# Connections_and_Power.net
KiCad netlist of a schematic drawn in EAGLE
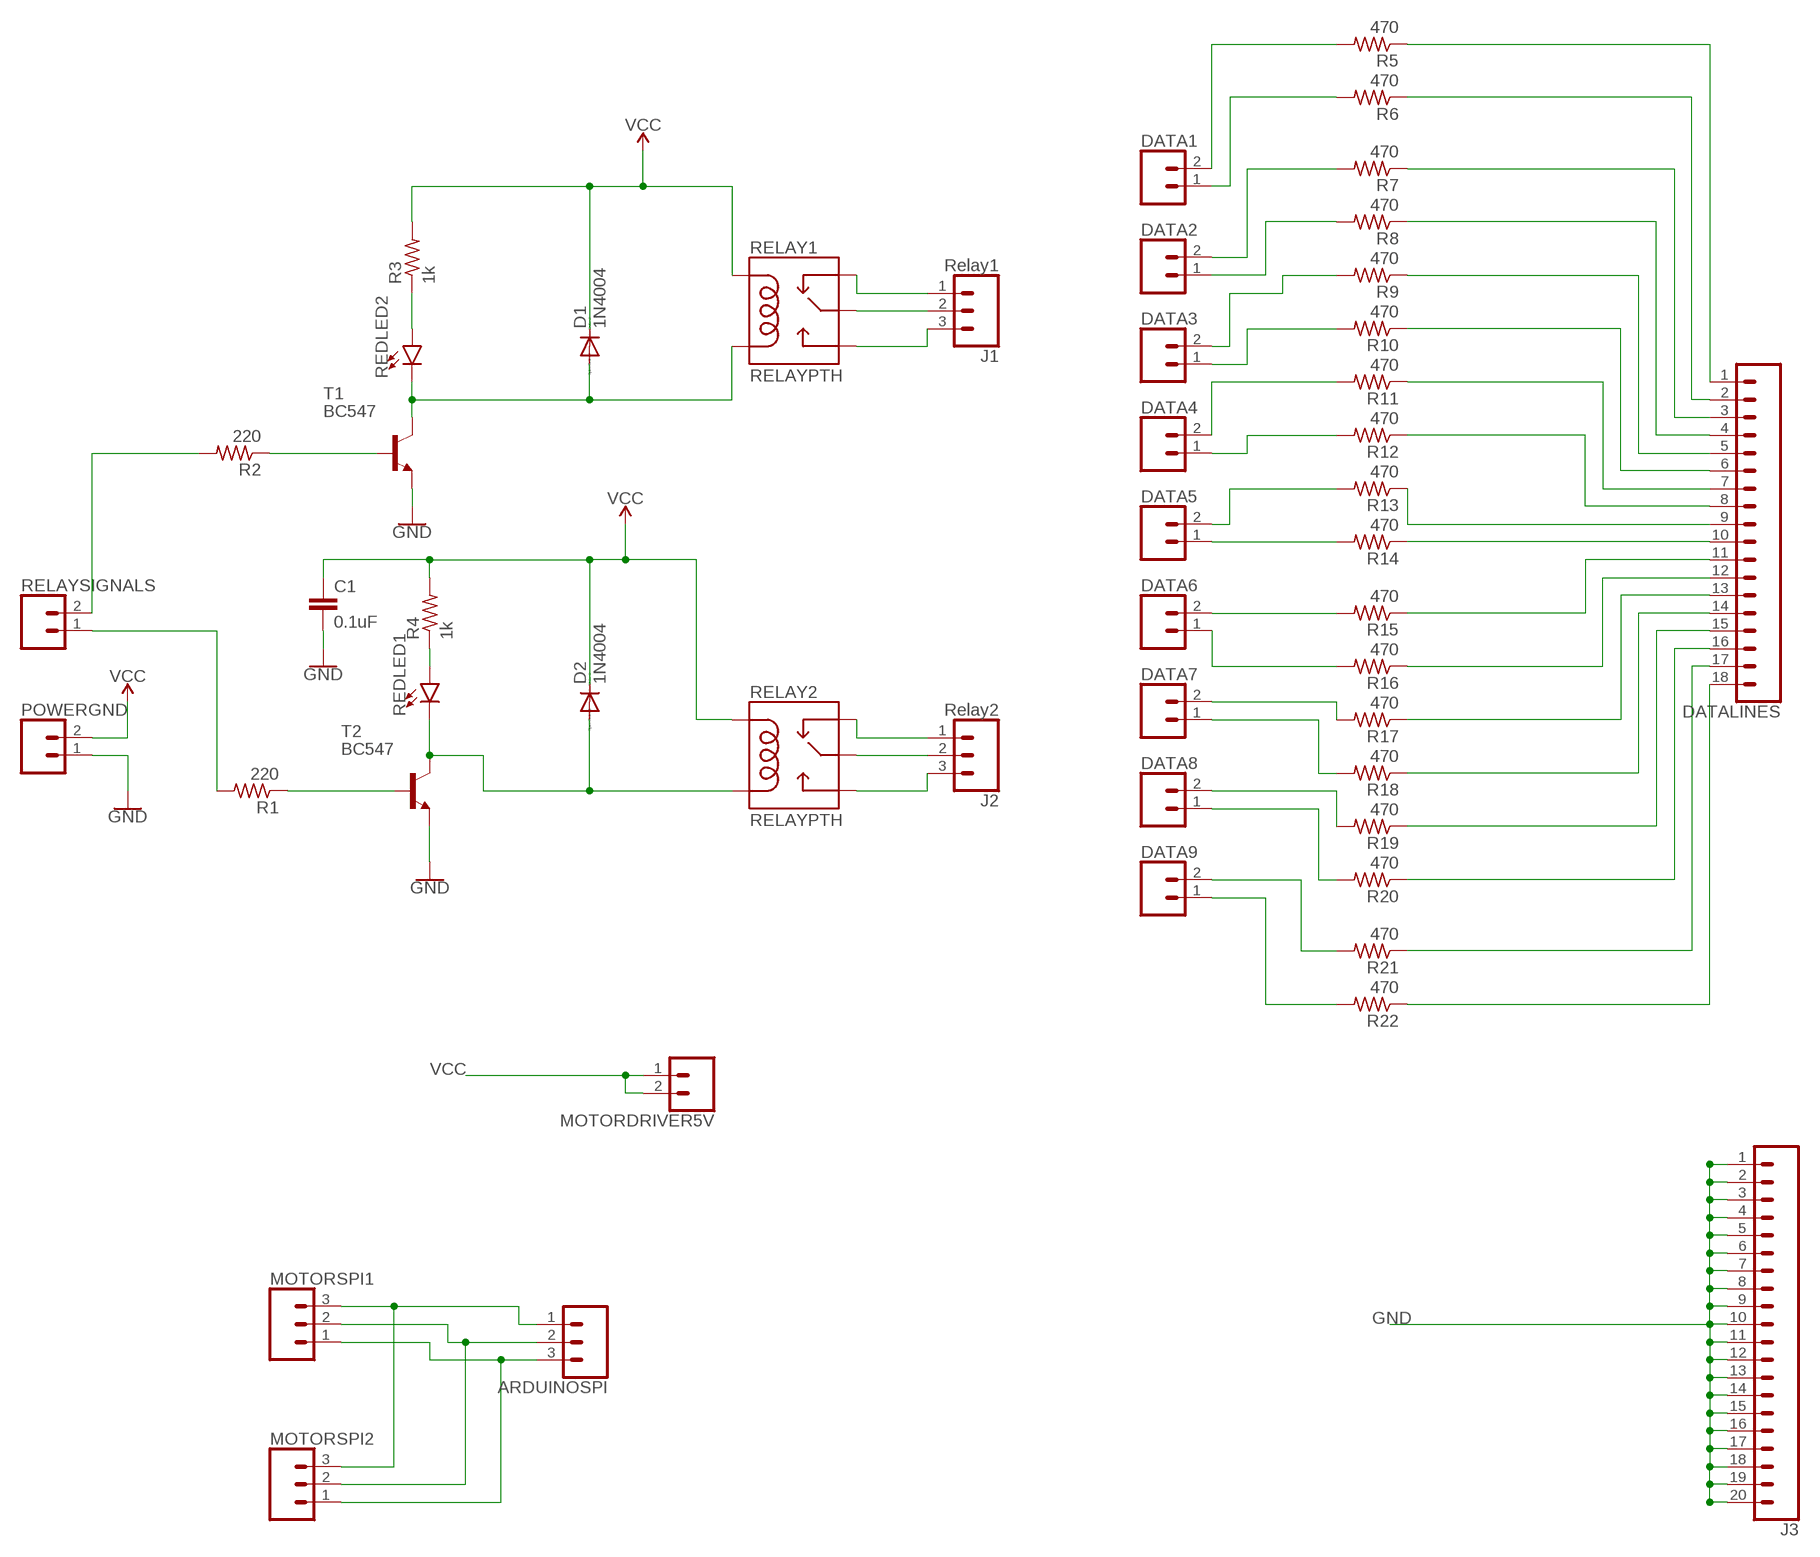
[diagram p0: schematic, sheet 1]

(export (version "E")
  (design (tool "Eeschema 10.0.6"))
  (components
    (comp (ref "ARDUINOSPI")
      (value "CONN_03")
      (footprint "eagle-import:1X03")
      (libsource (lib "eagle-import") (part "CONN_03"))
    )
    (comp (ref "C1")
      (value "0.1uF")
      (footprint "eagle-import:CAP-PTH-SMALL-KIT")
      (libsource (lib "eagle-import") (part "0.1UF-KIT-EZ-50V-20%"))
    )
    (comp (ref "D1")
      (value "1N4004")
      (footprint "eagle-import:DO41-10")
      (libsource (lib "eagle-import") (part "1N4004"))
    )
    (comp (ref "D2")
      (value "1N4004")
      (footprint "eagle-import:DO41-10")
      (libsource (lib "eagle-import") (part "1N4004"))
    )
    (comp (ref "DATA1")
      (value "CONN_023.5MM")
      (footprint "eagle-import:SCREWTERMINAL-3.5MM-2")
      (libsource (lib "eagle-import") (part "CONN_023.5MM"))
    )
    (comp (ref "DATA2")
      (value "CONN_023.5MM")
      (footprint "eagle-import:SCREWTERMINAL-3.5MM-2")
      (libsource (lib "eagle-import") (part "CONN_023.5MM"))
    )
    (comp (ref "DATA3")
      (value "CONN_023.5MM")
      (footprint "eagle-import:SCREWTERMINAL-3.5MM-2")
      (libsource (lib "eagle-import") (part "CONN_023.5MM"))
    )
    (comp (ref "DATA4")
      (value "CONN_023.5MM")
      (footprint "eagle-import:SCREWTERMINAL-3.5MM-2")
      (libsource (lib "eagle-import") (part "CONN_023.5MM"))
    )
    (comp (ref "DATA5")
      (value "CONN_023.5MM")
      (footprint "eagle-import:SCREWTERMINAL-3.5MM-2")
      (libsource (lib "eagle-import") (part "CONN_023.5MM"))
    )
    (comp (ref "DATA6")
      (value "CONN_023.5MM")
      (footprint "eagle-import:SCREWTERMINAL-3.5MM-2")
      (libsource (lib "eagle-import") (part "CONN_023.5MM"))
    )
    (comp (ref "DATA7")
      (value "CONN_023.5MM")
      (footprint "eagle-import:SCREWTERMINAL-3.5MM-2")
      (libsource (lib "eagle-import") (part "CONN_023.5MM"))
    )
    (comp (ref "DATA8")
      (value "CONN_023.5MM")
      (footprint "eagle-import:SCREWTERMINAL-3.5MM-2")
      (libsource (lib "eagle-import") (part "CONN_023.5MM"))
    )
    (comp (ref "DATA9")
      (value "CONN_023.5MM")
      (footprint "eagle-import:SCREWTERMINAL-3.5MM-2")
      (libsource (lib "eagle-import") (part "CONN_023.5MM"))
    )
    (comp (ref "DATALINES")
      (value "CONN_18")
      (footprint "eagle-import:1X18")
      (libsource (lib "eagle-import") (part "CONN_18"))
    )
    (comp (ref "J1")
      (value "Relay1")
      (footprint "eagle-import:SCREWTERMINAL-5MM-3")
      (libsource (lib "eagle-import") (part "CONN_03-SCREW-5MM"))
    )
    (comp (ref "J2")
      (value "Relay2")
      (footprint "eagle-import:SCREWTERMINAL-5MM-3")
      (libsource (lib "eagle-import") (part "CONN_03-SCREW-5MM"))
    )
    (comp (ref "J3")
      (value "CONN_20")
      (footprint "eagle-import:1X20")
      (libsource (lib "eagle-import") (part "CONN_20"))
    )
    (comp (ref "MOTORDRIVER5V")
      (value "CONN_02")
      (footprint "eagle-import:1X02")
      (libsource (lib "eagle-import") (part "CONN_02"))
    )
    (comp (ref "MOTORSPI1")
      (value "CONN_03")
      (footprint "eagle-import:1X03")
      (libsource (lib "eagle-import") (part "CONN_03"))
    )
    (comp (ref "MOTORSPI2")
      (value "CONN_03")
      (footprint "eagle-import:1X03")
      (libsource (lib "eagle-import") (part "CONN_03"))
    )
    (comp (ref "POWERGND")
      (value "CONN_025MM")
      (footprint "eagle-import:SCREWTERMINAL-5MM-2")
      (libsource (lib "eagle-import") (part "CONN_025MM"))
    )
    (comp (ref "R1")
      (value "220")
      (footprint "eagle-import:0309_12")
      (libsource (lib "eagle-import") (part "R-US_0309/12"))
    )
    (comp (ref "R2")
      (value "220")
      (footprint "eagle-import:0309_12")
      (libsource (lib "eagle-import") (part "R-US_0309/12"))
    )
    (comp (ref "R3")
      (value "1k")
      (footprint "eagle-import:0309_12")
      (libsource (lib "eagle-import") (part "R-US_0309/12"))
    )
    (comp (ref "R4")
      (value "1k")
      (footprint "eagle-import:0309_12")
      (libsource (lib "eagle-import") (part "R-US_0309/12"))
    )
    (comp (ref "R5")
      (value "470")
      (footprint "eagle-import:0309_12")
      (libsource (lib "eagle-import") (part "R-US_0309/12"))
    )
    (comp (ref "R6")
      (value "470")
      (footprint "eagle-import:0309_12")
      (libsource (lib "eagle-import") (part "R-US_0309/12"))
    )
    (comp (ref "R7")
      (value "470")
      (footprint "eagle-import:0309_12")
      (libsource (lib "eagle-import") (part "R-US_0309/12"))
    )
    (comp (ref "R8")
      (value "470")
      (footprint "eagle-import:0309_12")
      (libsource (lib "eagle-import") (part "R-US_0309/12"))
    )
    (comp (ref "R9")
      (value "470")
      (footprint "eagle-import:0309_12")
      (libsource (lib "eagle-import") (part "R-US_0309/12"))
    )
    (comp (ref "R10")
      (value "470")
      (footprint "eagle-import:0309_12")
      (libsource (lib "eagle-import") (part "R-US_0309/12"))
    )
    (comp (ref "R11")
      (value "470")
      (footprint "eagle-import:0309_12")
      (libsource (lib "eagle-import") (part "R-US_0309/12"))
    )
    (comp (ref "R12")
      (value "470")
      (footprint "eagle-import:0309_12")
      (libsource (lib "eagle-import") (part "R-US_0309/12"))
    )
    (comp (ref "R13")
      (value "470")
      (footprint "eagle-import:0309_12")
      (libsource (lib "eagle-import") (part "R-US_0309/12"))
    )
    (comp (ref "R14")
      (value "470")
      (footprint "eagle-import:0309_12")
      (libsource (lib "eagle-import") (part "R-US_0309/12"))
    )
    (comp (ref "R15")
      (value "470")
      (footprint "eagle-import:0309_12")
      (libsource (lib "eagle-import") (part "R-US_0309/12"))
    )
    (comp (ref "R16")
      (value "470")
      (footprint "eagle-import:0309_12")
      (libsource (lib "eagle-import") (part "R-US_0309/12"))
    )
    (comp (ref "R17")
      (value "470")
      (footprint "eagle-import:0309_12")
      (libsource (lib "eagle-import") (part "R-US_0309/12"))
    )
    (comp (ref "R18")
      (value "470")
      (footprint "eagle-import:0309_12")
      (libsource (lib "eagle-import") (part "R-US_0309/12"))
    )
    (comp (ref "R19")
      (value "470")
      (footprint "eagle-import:0309_12")
      (libsource (lib "eagle-import") (part "R-US_0309/12"))
    )
    (comp (ref "R20")
      (value "470")
      (footprint "eagle-import:0309_12")
      (libsource (lib "eagle-import") (part "R-US_0309/12"))
    )
    (comp (ref "R21")
      (value "470")
      (footprint "eagle-import:0309_12")
      (libsource (lib "eagle-import") (part "R-US_0309/12"))
    )
    (comp (ref "R22")
      (value "470")
      (footprint "eagle-import:0309_12")
      (libsource (lib "eagle-import") (part "R-US_0309/12"))
    )
    (comp (ref "REDLED1")
      (value "LED1206")
      (footprint "eagle-import:LED-1206")
      (libsource (lib "eagle-import") (part "LED1206"))
    )
    (comp (ref "REDLED2")
      (value "LED1206")
      (footprint "eagle-import:LED-1206")
      (libsource (lib "eagle-import") (part "LED1206"))
    )
    (comp (ref "RELAY1")
      (value "RELAYPTH")
      (footprint "eagle-import:SRD-05VDC-SL-C")
      (libsource (lib "eagle-import") (part "RELAYPTH"))
    )
    (comp (ref "RELAY2")
      (value "RELAYPTH")
      (footprint "eagle-import:SRD-05VDC-SL-C")
      (libsource (lib "eagle-import") (part "RELAYPTH"))
    )
    (comp (ref "RELAYSIGNALS")
      (value "CONN_025MM")
      (footprint "eagle-import:SCREWTERMINAL-5MM-2")
      (libsource (lib "eagle-import") (part "CONN_025MM"))
    )
    (comp (ref "T1")
      (value "BC547")
      (footprint "eagle-import:TO92")
      (libsource (lib "eagle-import") (part "BC547"))
    )
    (comp (ref "T2")
      (value "BC547")
      (footprint "eagle-import:TO92")
      (libsource (lib "eagle-import") (part "BC547"))
    )
  )
  (nets
    (net (code "1") (name "GND") (class "Default")
      (node (ref "C1") (pin "2") (pinfunction "2_2") (pintype "passive"))
      (node (ref "J3") (pin "1") (pinfunction "1_1") (pintype "passive"))
      (node (ref "J3") (pin "10") (pinfunction "10_10") (pintype "passive"))
      (node (ref "J3") (pin "11") (pinfunction "11_11") (pintype "passive"))
      (node (ref "J3") (pin "12") (pinfunction "12_12") (pintype "passive"))
      (node (ref "J3") (pin "13") (pinfunction "13_13") (pintype "passive"))
      (node (ref "J3") (pin "14") (pinfunction "14_14") (pintype "passive"))
      (node (ref "J3") (pin "15") (pinfunction "15_15") (pintype "passive"))
      (node (ref "J3") (pin "16") (pinfunction "16_16") (pintype "passive"))
      (node (ref "J3") (pin "17") (pinfunction "17_17") (pintype "passive"))
      (node (ref "J3") (pin "18") (pinfunction "18_18") (pintype "passive"))
      (node (ref "J3") (pin "19") (pinfunction "19_19") (pintype "passive"))
      (node (ref "J3") (pin "2") (pinfunction "2_2") (pintype "passive"))
      (node (ref "J3") (pin "20") (pinfunction "20_20") (pintype "passive"))
      (node (ref "J3") (pin "3") (pinfunction "3_3") (pintype "passive"))
      (node (ref "J3") (pin "4") (pinfunction "4_4") (pintype "passive"))
      (node (ref "J3") (pin "5") (pinfunction "5_5") (pintype "passive"))
      (node (ref "J3") (pin "6") (pinfunction "6_6") (pintype "passive"))
      (node (ref "J3") (pin "7") (pinfunction "7_7") (pintype "passive"))
      (node (ref "J3") (pin "8") (pinfunction "8_8") (pintype "passive"))
      (node (ref "J3") (pin "9") (pinfunction "9_9") (pintype "passive"))
      (node (ref "POWERGND") (pin "1") (pinfunction "1_1") (pintype "passive"))
      (node (ref "T1") (pin "1") (pinfunction "E_1") (pintype "passive"))
      (node (ref "T2") (pin "1") (pinfunction "E_1") (pintype "passive"))
    )
    (net (code "2") (name "Net-(ARDUINOSPI-Pad1)") (class "Default")
      (node (ref "ARDUINOSPI") (pin "1") (pinfunction "1_1") (pintype "passive"))
      (node (ref "MOTORSPI1") (pin "3") (pinfunction "3_3") (pintype "passive"))
      (node (ref "MOTORSPI2") (pin "3") (pinfunction "3_3") (pintype "passive"))
    )
    (net (code "3") (name "Net-(ARDUINOSPI-Pad2)") (class "Default")
      (node (ref "ARDUINOSPI") (pin "2") (pinfunction "2_2") (pintype "passive"))
      (node (ref "MOTORSPI1") (pin "2") (pinfunction "2_2") (pintype "passive"))
      (node (ref "MOTORSPI2") (pin "2") (pinfunction "2_2") (pintype "passive"))
    )
    (net (code "4") (name "Net-(ARDUINOSPI-Pad3)") (class "Default")
      (node (ref "ARDUINOSPI") (pin "3") (pinfunction "3_3") (pintype "passive"))
      (node (ref "MOTORSPI1") (pin "1") (pinfunction "1_1") (pintype "passive"))
      (node (ref "MOTORSPI2") (pin "1") (pinfunction "1_1") (pintype "passive"))
    )
    (net (code "5") (name "Net-(DATA1-Pad1)") (class "Default")
      (node (ref "DATA1") (pin "1") (pinfunction "1_1") (pintype "passive"))
      (node (ref "R6") (pin "2") (pinfunction "2_2") (pintype "passive"))
    )
    (net (code "6") (name "Net-(DATA1-Pad2)") (class "Default")
      (node (ref "DATA1") (pin "2") (pinfunction "2_2") (pintype "passive"))
      (node (ref "R5") (pin "2") (pinfunction "2_2") (pintype "passive"))
    )
    (net (code "7") (name "Net-(DATA2-Pad1)") (class "Default")
      (node (ref "DATA2") (pin "1") (pinfunction "1_1") (pintype "passive"))
      (node (ref "R8") (pin "2") (pinfunction "2_2") (pintype "passive"))
    )
    (net (code "8") (name "Net-(DATA2-Pad2)") (class "Default")
      (node (ref "DATA2") (pin "2") (pinfunction "2_2") (pintype "passive"))
      (node (ref "R7") (pin "2") (pinfunction "2_2") (pintype "passive"))
    )
    (net (code "9") (name "Net-(DATA3-Pad1)") (class "Default")
      (node (ref "DATA3") (pin "1") (pinfunction "1_1") (pintype "passive"))
      (node (ref "R10") (pin "2") (pinfunction "2_2") (pintype "passive"))
    )
    (net (code "10") (name "Net-(DATA3-Pad2)") (class "Default")
      (node (ref "DATA3") (pin "2") (pinfunction "2_2") (pintype "passive"))
      (node (ref "R9") (pin "2") (pinfunction "2_2") (pintype "passive"))
    )
    (net (code "11") (name "Net-(DATA4-Pad1)") (class "Default")
      (node (ref "DATA4") (pin "1") (pinfunction "1_1") (pintype "passive"))
      (node (ref "R12") (pin "2") (pinfunction "2_2") (pintype "passive"))
    )
    (net (code "12") (name "Net-(DATA4-Pad2)") (class "Default")
      (node (ref "DATA4") (pin "2") (pinfunction "2_2") (pintype "passive"))
      (node (ref "R11") (pin "2") (pinfunction "2_2") (pintype "passive"))
    )
    (net (code "13") (name "Net-(DATA5-Pad1)") (class "Default")
      (node (ref "DATA5") (pin "1") (pinfunction "1_1") (pintype "passive"))
      (node (ref "R14") (pin "2") (pinfunction "2_2") (pintype "passive"))
    )
    (net (code "14") (name "Net-(DATA5-Pad2)") (class "Default")
      (node (ref "DATA5") (pin "2") (pinfunction "2_2") (pintype "passive"))
      (node (ref "R13") (pin "2") (pinfunction "2_2") (pintype "passive"))
    )
    (net (code "15") (name "Net-(DATA6-Pad1)") (class "Default")
      (node (ref "DATA6") (pin "1") (pinfunction "1_1") (pintype "passive"))
      (node (ref "R16") (pin "2") (pinfunction "2_2") (pintype "passive"))
    )
    (net (code "16") (name "Net-(DATA6-Pad2)") (class "Default")
      (node (ref "DATA6") (pin "2") (pinfunction "2_2") (pintype "passive"))
      (node (ref "R15") (pin "2") (pinfunction "2_2") (pintype "passive"))
    )
    (net (code "17") (name "Net-(DATA7-Pad1)") (class "Default")
      (node (ref "DATA7") (pin "1") (pinfunction "1_1") (pintype "passive"))
      (node (ref "R18") (pin "2") (pinfunction "2_2") (pintype "passive"))
    )
    (net (code "18") (name "Net-(DATA7-Pad2)") (class "Default")
      (node (ref "DATA7") (pin "2") (pinfunction "2_2") (pintype "passive"))
      (node (ref "R17") (pin "2") (pinfunction "2_2") (pintype "passive"))
    )
    (net (code "19") (name "Net-(DATA8-Pad1)") (class "Default")
      (node (ref "DATA8") (pin "1") (pinfunction "1_1") (pintype "passive"))
      (node (ref "R20") (pin "2") (pinfunction "2_2") (pintype "passive"))
    )
    (net (code "20") (name "Net-(DATA8-Pad2)") (class "Default")
      (node (ref "DATA8") (pin "2") (pinfunction "2_2") (pintype "passive"))
      (node (ref "R19") (pin "2") (pinfunction "2_2") (pintype "passive"))
    )
    (net (code "21") (name "Net-(DATA9-Pad1)") (class "Default")
      (node (ref "DATA9") (pin "1") (pinfunction "1_1") (pintype "passive"))
      (node (ref "R22") (pin "2") (pinfunction "2_2") (pintype "passive"))
    )
    (net (code "22") (name "Net-(DATA9-Pad2)") (class "Default")
      (node (ref "DATA9") (pin "2") (pinfunction "2_2") (pintype "passive"))
      (node (ref "R21") (pin "2") (pinfunction "2_2") (pintype "passive"))
    )
    (net (code "23") (name "Net-(DATALINES-Pad1)") (class "Default")
      (node (ref "DATALINES") (pin "1") (pinfunction "1_1") (pintype "passive"))
      (node (ref "R5") (pin "1") (pinfunction "1_1") (pintype "passive"))
    )
    (net (code "24") (name "Net-(DATALINES-Pad2)") (class "Default")
      (node (ref "DATALINES") (pin "2") (pinfunction "2_2") (pintype "passive"))
      (node (ref "R6") (pin "1") (pinfunction "1_1") (pintype "passive"))
    )
    (net (code "25") (name "Net-(DATALINES-Pad3)") (class "Default")
      (node (ref "DATALINES") (pin "3") (pinfunction "3_3") (pintype "passive"))
      (node (ref "R7") (pin "1") (pinfunction "1_1") (pintype "passive"))
    )
    (net (code "26") (name "Net-(DATALINES-Pad4)") (class "Default")
      (node (ref "DATALINES") (pin "4") (pinfunction "4_4") (pintype "passive"))
      (node (ref "R8") (pin "1") (pinfunction "1_1") (pintype "passive"))
    )
    (net (code "27") (name "Net-(DATALINES-Pad5)") (class "Default")
      (node (ref "DATALINES") (pin "5") (pinfunction "5_5") (pintype "passive"))
      (node (ref "R9") (pin "1") (pinfunction "1_1") (pintype "passive"))
    )
    (net (code "28") (name "Net-(DATALINES-Pad6)") (class "Default")
      (node (ref "DATALINES") (pin "6") (pinfunction "6_6") (pintype "passive"))
      (node (ref "R10") (pin "1") (pinfunction "1_1") (pintype "passive"))
    )
    (net (code "29") (name "Net-(DATALINES-Pad7)") (class "Default")
      (node (ref "DATALINES") (pin "7") (pinfunction "7_7") (pintype "passive"))
      (node (ref "R11") (pin "1") (pinfunction "1_1") (pintype "passive"))
    )
    (net (code "30") (name "Net-(DATALINES-Pad8)") (class "Default")
      (node (ref "DATALINES") (pin "8") (pinfunction "8_8") (pintype "passive"))
      (node (ref "R12") (pin "1") (pinfunction "1_1") (pintype "passive"))
    )
    (net (code "31") (name "Net-(DATALINES-Pad9)") (class "Default")
      (node (ref "DATALINES") (pin "9") (pinfunction "9_9") (pintype "passive"))
      (node (ref "R13") (pin "1") (pinfunction "1_1") (pintype "passive"))
    )
    (net (code "32") (name "Net-(DATALINES-Pad10)") (class "Default")
      (node (ref "DATALINES") (pin "10") (pinfunction "10_10") (pintype "passive"))
      (node (ref "R14") (pin "1") (pinfunction "1_1") (pintype "passive"))
    )
    (net (code "33") (name "Net-(DATALINES-Pad11)") (class "Default")
      (node (ref "DATALINES") (pin "11") (pinfunction "11_11") (pintype "passive"))
      (node (ref "R15") (pin "1") (pinfunction "1_1") (pintype "passive"))
    )
    (net (code "34") (name "Net-(DATALINES-Pad12)") (class "Default")
      (node (ref "DATALINES") (pin "12") (pinfunction "12_12") (pintype "passive"))
      (node (ref "R16") (pin "1") (pinfunction "1_1") (pintype "passive"))
    )
    (net (code "35") (name "Net-(DATALINES-Pad13)") (class "Default")
      (node (ref "DATALINES") (pin "13") (pinfunction "13_13") (pintype "passive"))
      (node (ref "R17") (pin "1") (pinfunction "1_1") (pintype "passive"))
    )
    (net (code "36") (name "Net-(DATALINES-Pad14)") (class "Default")
      (node (ref "DATALINES") (pin "14") (pinfunction "14_14") (pintype "passive"))
      (node (ref "R18") (pin "1") (pinfunction "1_1") (pintype "passive"))
    )
    (net (code "37") (name "Net-(DATALINES-Pad15)") (class "Default")
      (node (ref "DATALINES") (pin "15") (pinfunction "15_15") (pintype "passive"))
      (node (ref "R19") (pin "1") (pinfunction "1_1") (pintype "passive"))
    )
    (net (code "38") (name "Net-(DATALINES-Pad16)") (class "Default")
      (node (ref "DATALINES") (pin "16") (pinfunction "16_16") (pintype "passive"))
      (node (ref "R20") (pin "1") (pinfunction "1_1") (pintype "passive"))
    )
    (net (code "39") (name "Net-(DATALINES-Pad17)") (class "Default")
      (node (ref "DATALINES") (pin "17") (pinfunction "17_17") (pintype "passive"))
      (node (ref "R21") (pin "1") (pinfunction "1_1") (pintype "passive"))
    )
    (net (code "40") (name "Net-(DATALINES-Pad18)") (class "Default")
      (node (ref "DATALINES") (pin "18") (pinfunction "18_18") (pintype "passive"))
      (node (ref "R22") (pin "1") (pinfunction "1_1") (pintype "passive"))
    )
    (net (code "41") (name "Net-(J1-Pad2)") (class "Default")
      (node (ref "J1") (pin "2") (pinfunction "2_2") (pintype "passive"))
      (node (ref "RELAY1") (pin "SWCOMMON") (pinfunction "SWCOMMON_SWCOMMON") (pintype "bidirectional"))
    )
    (net (code "42") (name "Net-(J1-Pad3)") (class "Default")
      (node (ref "J1") (pin "3") (pinfunction "3_3") (pintype "passive"))
      (node (ref "RELAY1") (pin "SWOPEN") (pinfunction "SWOPEN_SWOPEN") (pintype "bidirectional"))
    )
    (net (code "43") (name "Net-(J2-Pad2)") (class "Default")
      (node (ref "J2") (pin "2") (pinfunction "2_2") (pintype "passive"))
      (node (ref "RELAY2") (pin "SWCOMMON") (pinfunction "SWCOMMON_SWCOMMON") (pintype "bidirectional"))
    )
    (net (code "44") (name "Net-(J2-Pad3)") (class "Default")
      (node (ref "J2") (pin "3") (pinfunction "3_3") (pintype "passive"))
      (node (ref "RELAY2") (pin "SWOPEN") (pinfunction "SWOPEN_SWOPEN") (pintype "bidirectional"))
    )
    (net (code "45") (name "Net-(R1-Pad2)") (class "Default")
      (node (ref "R1") (pin "2") (pinfunction "2_2") (pintype "passive"))
      (node (ref "RELAYSIGNALS") (pin "1") (pinfunction "1_1") (pintype "passive"))
    )
    (net (code "46") (name "Net-(R2-Pad2)") (class "Default")
      (node (ref "R2") (pin "2") (pinfunction "2_2") (pintype "passive"))
      (node (ref "RELAYSIGNALS") (pin "2") (pinfunction "2_2") (pintype "passive"))
    )
    (net (code "47") (name "Net-(R3-Pad1)") (class "Default")
      (node (ref "R3") (pin "1") (pinfunction "1_1") (pintype "passive"))
      (node (ref "REDLED2") (pin "A") (pinfunction "A_A") (pintype "passive"))
    )
    (net (code "48") (name "Net-(R4-Pad1)") (class "Default")
      (node (ref "R4") (pin "1") (pinfunction "1_1") (pintype "passive"))
      (node (ref "REDLED1") (pin "A") (pinfunction "A_A") (pintype "passive"))
    )
    (net (code "49") (name "Net-(RELAY1-SWCLOSE)") (class "Default")
      (node (ref "J1") (pin "1") (pinfunction "1_1") (pintype "passive"))
      (node (ref "RELAY1") (pin "SWCLOSED") (pinfunction "SWCLOSE_SWCLOSED") (pintype "bidirectional"))
    )
    (net (code "50") (name "Net-(RELAY2-SWCLOSE)") (class "Default")
      (node (ref "J2") (pin "1") (pinfunction "1_1") (pintype "passive"))
      (node (ref "RELAY2") (pin "SWCLOSED") (pinfunction "SWCLOSE_SWCLOSED") (pintype "bidirectional"))
    )
    (net (code "51") (name "Net-(T1-B)") (class "Default")
      (node (ref "R2") (pin "1") (pinfunction "1_1") (pintype "passive"))
      (node (ref "T1") (pin "2") (pinfunction "B_2") (pintype "passive"))
    )
    (net (code "52") (name "Net-(T1-C)") (class "Default")
      (node (ref "D1") (pin "A") (pinfunction "A_A") (pintype "passive"))
      (node (ref "REDLED2") (pin "C") (pinfunction "C_C") (pintype "passive"))
      (node (ref "RELAY1") (pin "COIL0") (pinfunction "COIL0_COIL0") (pintype "bidirectional"))
      (node (ref "T1") (pin "3") (pinfunction "C_3") (pintype "passive"))
    )
    (net (code "53") (name "Net-(T2-B)") (class "Default")
      (node (ref "R1") (pin "1") (pinfunction "1_1") (pintype "passive"))
      (node (ref "T2") (pin "2") (pinfunction "B_2") (pintype "passive"))
    )
    (net (code "54") (name "Net-(T2-C)") (class "Default")
      (node (ref "D2") (pin "A") (pinfunction "A_A") (pintype "passive"))
      (node (ref "REDLED1") (pin "C") (pinfunction "C_C") (pintype "passive"))
      (node (ref "RELAY2") (pin "COIL0") (pinfunction "COIL0_COIL0") (pintype "bidirectional"))
      (node (ref "T2") (pin "3") (pinfunction "C_3") (pintype "passive"))
    )
    (net (code "55") (name "VCC") (class "Default")
      (node (ref "C1") (pin "1") (pinfunction "1_1") (pintype "passive"))
      (node (ref "D1") (pin "C") (pinfunction "C_C") (pintype "passive"))
      (node (ref "D2") (pin "C") (pinfunction "C_C") (pintype "passive"))
      (node (ref "MOTORDRIVER5V") (pin "1") (pinfunction "1_1") (pintype "passive"))
      (node (ref "MOTORDRIVER5V") (pin "2") (pinfunction "2_2") (pintype "passive"))
      (node (ref "POWERGND") (pin "2") (pinfunction "2_2") (pintype "passive"))
      (node (ref "R3") (pin "2") (pinfunction "2_2") (pintype "passive"))
      (node (ref "R4") (pin "2") (pinfunction "2_2") (pintype "passive"))
      (node (ref "RELAY1") (pin "COIL1") (pinfunction "COIL1_COIL1") (pintype "bidirectional"))
      (node (ref "RELAY2") (pin "COIL1") (pinfunction "COIL1_COIL1") (pintype "bidirectional"))
    )
  )
)
